# AQS-v4_0.net
KiCad netlist of a schematic drawn in EAGLE
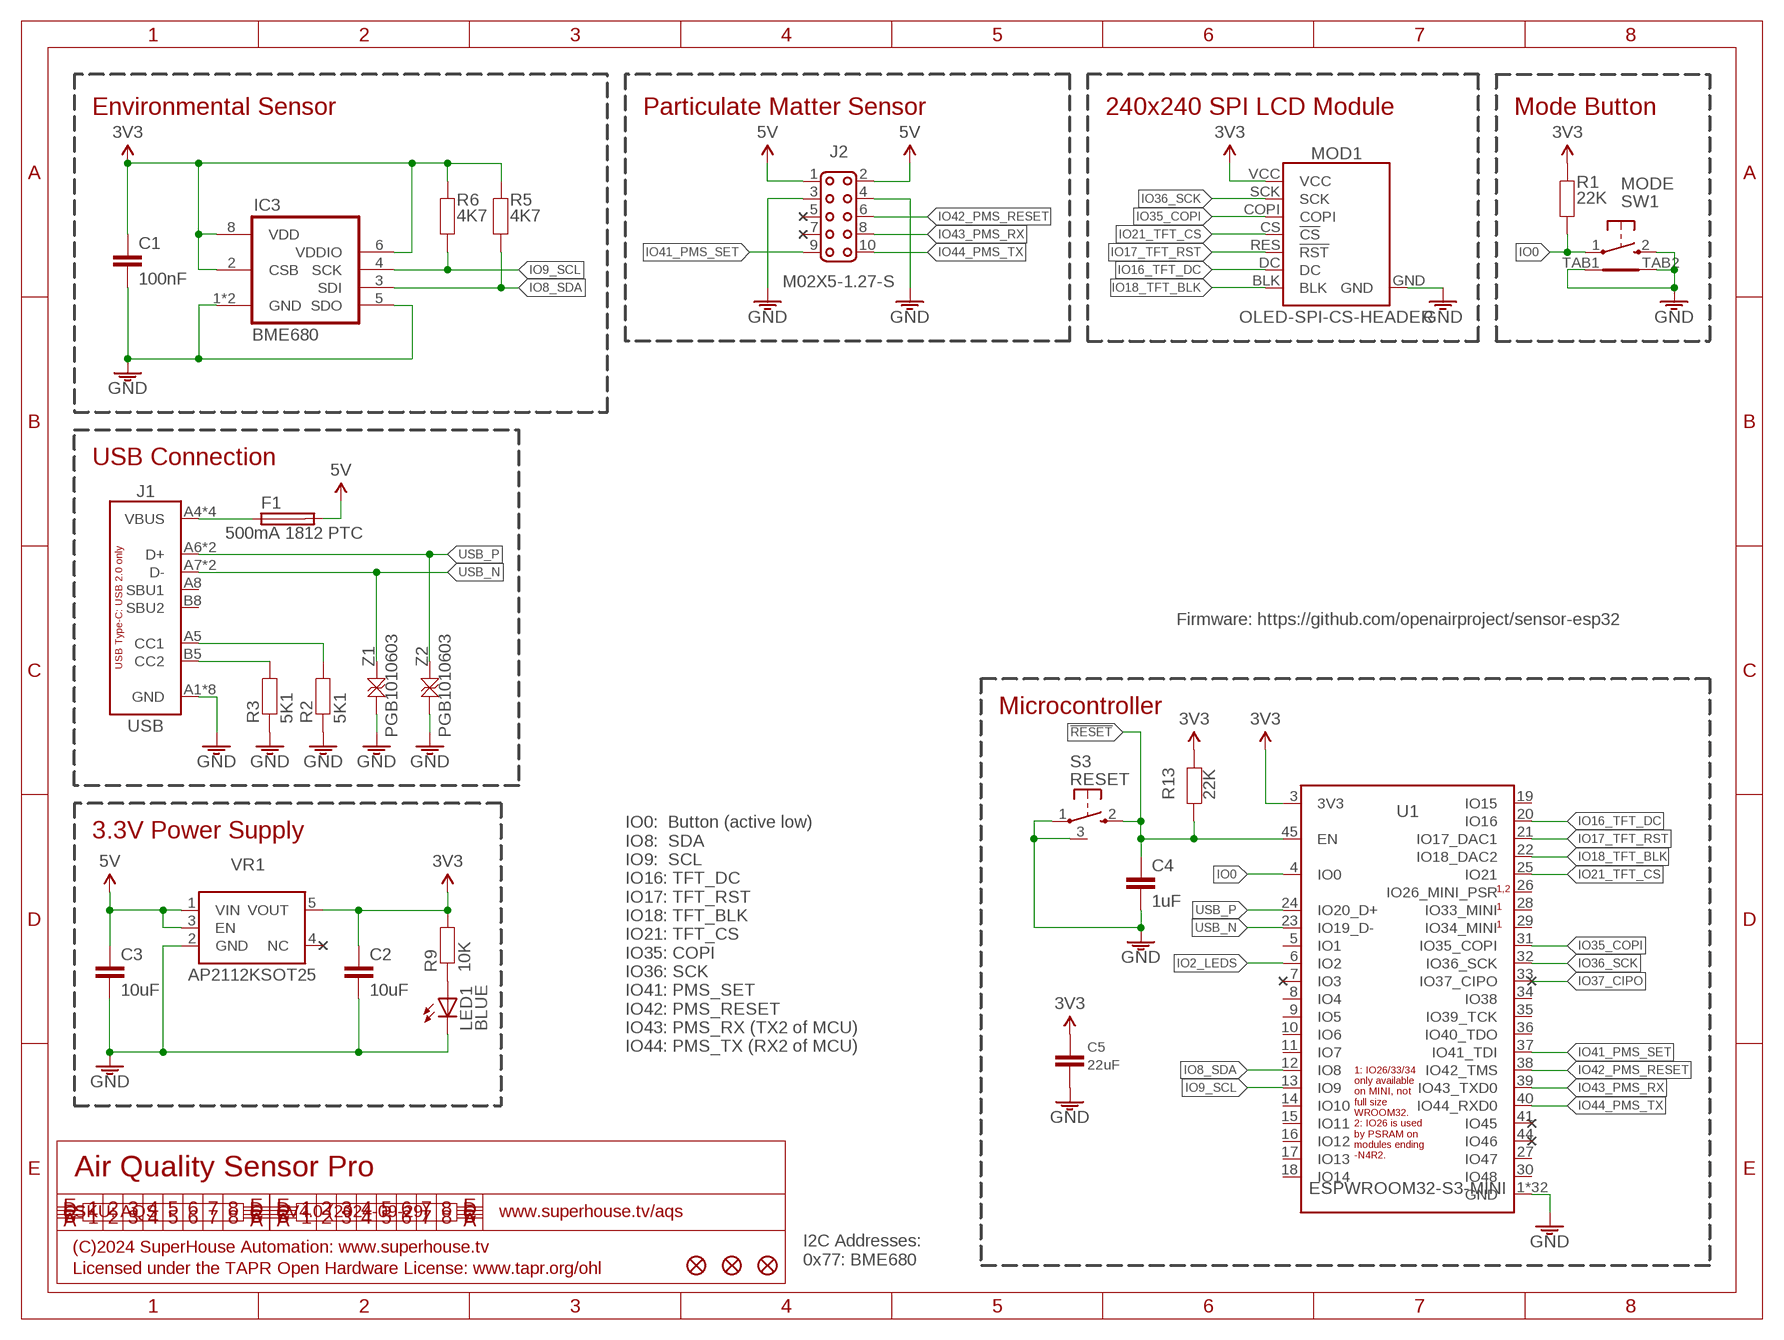
[diagram p0: schematic, sheet 1]

(export (version "E")
  (design (tool "Eeschema 10.0.6"))
  (components
    (comp (ref "C1")
      (value "100nF")
      (footprint "eagle-import:C0603")
      (libsource (lib "eagle-import") (part "CAP0603"))
    )
    (comp (ref "C2")
      (value "10uF")
      (footprint "eagle-import:C0805")
      (libsource (lib "eagle-import") (part "CAP0805"))
    )
    (comp (ref "C3")
      (value "10uF")
      (footprint "eagle-import:C0805")
      (libsource (lib "eagle-import") (part "CAP0805"))
    )
    (comp (ref "C4")
      (value "1uF")
      (footprint "eagle-import:C0603")
      (libsource (lib "eagle-import") (part "CAP0603"))
    )
    (comp (ref "C5")
      (value "22uF")
      (footprint "eagle-import:C0805")
      (libsource (lib "eagle-import") (part "CAP0805"))
    )
    (comp (ref "F1")
      (value "500mA 1812 PTC")
      (footprint "eagle-import:1206")
      (libsource (lib "eagle-import") (part "PTC-1206"))
    )
    (comp (ref "IC3")
      (value "BME680")
      (footprint "eagle-import:BME680")
      (libsource (lib "eagle-import") (part "BME680"))
    )
    (comp (ref "J1")
      (value "USB")
      (footprint "eagle-import:USB-C-VERT")
      (libsource (lib "eagle-import") (part "USB-C-16P-16P-VERT"))
    )
    (comp (ref "J2")
      (value "M02X5-1.27-S")
      (footprint "eagle-import:2X05-1.27-S")
      (libsource (lib "eagle-import") (part "M02X5-1.27-S"))
    )
    (comp (ref "LED1")
      (value "BLUE")
      (footprint "eagle-import:LED-0603")
      (libsource (lib "eagle-import") (part "LED0603"))
    )
    (comp (ref "MOD1")
      (value "OLED-SPI-CS-HEADER")
      (footprint "eagle-import:OLED-240X240-1.54-HEADER")
      (libsource (lib "eagle-import") (part "OLED-SPI-CS-HEADER"))
    )
    (comp (ref "R1")
      (value "22K")
      (footprint "eagle-import:R0603")
      (libsource (lib "eagle-import") (part "RESISTOR0603"))
    )
    (comp (ref "R2")
      (value "5K1")
      (footprint "eagle-import:R0603")
      (libsource (lib "eagle-import") (part "RESISTOR0603"))
    )
    (comp (ref "R3")
      (value "5K1")
      (footprint "eagle-import:R0603")
      (libsource (lib "eagle-import") (part "RESISTOR0603"))
    )
    (comp (ref "R5")
      (value "4K7")
      (footprint "eagle-import:R0603")
      (libsource (lib "eagle-import") (part "RESISTOR0603"))
    )
    (comp (ref "R6")
      (value "4K7")
      (footprint "eagle-import:R0603")
      (libsource (lib "eagle-import") (part "RESISTOR0603"))
    )
    (comp (ref "R9")
      (value "10K")
      (footprint "eagle-import:R0603")
      (libsource (lib "eagle-import") (part "RESISTOR0603"))
    )
    (comp (ref "R13")
      (value "22K")
      (footprint "eagle-import:R0603")
      (libsource (lib "eagle-import") (part "RESISTOR0603"))
    )
    (comp (ref "S3")
      (value "RESET")
      (footprint "eagle-import:TACT-VERT-1TAB")
      (libsource (lib "eagle-import") (part "TAC-SWITCH-1TABGT-TCB73B"))
    )
    (comp (ref "SW1")
      (value "MODE")
      (footprint "eagle-import:TYCO-FSMRAJ")
      (libsource (lib "eagle-import") (part "TAC-SWITCH-2PIN-GND-FSMRAJ"))
    )
    (comp (ref "U$23")
      (value "FIDUCIAL1X2")
      (footprint "eagle-import:FIDUCIAL-1X2")
      (libsource (lib "eagle-import") (part "FIDUCIAL1X2"))
    )
    (comp (ref "U$24")
      (value "FIDUCIAL1X2")
      (footprint "eagle-import:FIDUCIAL-1X2")
      (libsource (lib "eagle-import") (part "FIDUCIAL1X2"))
    )
    (comp (ref "U$25")
      (value "FIDUCIAL1X2")
      (footprint "eagle-import:FIDUCIAL-1X2")
      (libsource (lib "eagle-import") (part "FIDUCIAL1X2"))
    )
    (comp (ref "U1")
      (value "ESPWROOM32-S3-MINI")
      (footprint "eagle-import:ESP32-S3-MINI")
      (libsource (lib "eagle-import") (part "ESPWROOM32-S3-MINI"))
    )
    (comp (ref "VR1")
      (value "AP2112KSOT25")
      (footprint "eagle-import:SOT23-5")
      (libsource (lib "eagle-import") (part "AP2112KSOT25"))
    )
    (comp (ref "Z1")
      (value "PGB1010603")
      (footprint "eagle-import:TVS0603")
      (libsource (lib "eagle-import") (part "TVS0603"))
    )
    (comp (ref "Z2")
      (value "PGB1010603")
      (footprint "eagle-import:TVS0603")
      (libsource (lib "eagle-import") (part "TVS0603"))
    )
  )
  (nets
    (net (code "1") (name "/IO46") (class "Default")
      (node (ref "U1") (pin "44") (pinfunction "IO46_44") (pintype "power_in"))
    )
    (net (code "2") (name "/~{RESET}") (class "Default")
      (node (ref "C4") (pin "1") (pinfunction "1_1") (pintype "passive"))
      (node (ref "R13") (pin "2") (pinfunction "2_2") (pintype "passive"))
      (node (ref "S3") (pin "2") (pinfunction "2_2") (pintype "passive"))
      (node (ref "U1") (pin "45") (pinfunction "EN_45") (pintype "bidirectional"))
    )
    (net (code "3") (name "3.3V") (class "Default")
      (node (ref "C1") (pin "1") (pinfunction "1_1") (pintype "passive"))
      (node (ref "C2") (pin "1") (pinfunction "1_1") (pintype "passive"))
      (node (ref "C5") (pin "1") (pinfunction "1_1") (pintype "passive"))
      (node (ref "IC3") (pin "2") (pinfunction "CSB_2") (pintype "input"))
      (node (ref "IC3") (pin "6") (pinfunction "VDDIO_6") (pintype "power_in"))
      (node (ref "IC3") (pin "8") (pinfunction "VDD_8") (pintype "power_in"))
      (node (ref "MOD1") (pin "VCC") (pinfunction "VCC_VCC") (pintype "bidirectional"))
      (node (ref "R1") (pin "2") (pinfunction "2_2") (pintype "passive"))
      (node (ref "R13") (pin "1") (pinfunction "1_1") (pintype "passive"))
      (node (ref "R5") (pin "2") (pinfunction "2_2") (pintype "passive"))
      (node (ref "R6") (pin "2") (pinfunction "2_2") (pintype "passive"))
      (node (ref "R9") (pin "2") (pinfunction "2_2") (pintype "passive"))
      (node (ref "U1") (pin "3") (pinfunction "3V3_3") (pintype "power_in"))
      (node (ref "VR1") (pin "5") (pinfunction "VOUT_5") (pintype "bidirectional"))
    )
    (net (code "4") (name "5V") (class "Default")
      (node (ref "C3") (pin "1") (pinfunction "1_1") (pintype "passive"))
      (node (ref "F1") (pin "2") (pinfunction "2_2") (pintype "passive"))
      (node (ref "J2") (pin "1") (pinfunction "1_1") (pintype "passive"))
      (node (ref "J2") (pin "2") (pinfunction "2_2") (pintype "passive"))
      (node (ref "VR1") (pin "1") (pinfunction "VIN_1") (pintype "bidirectional"))
      (node (ref "VR1") (pin "3") (pinfunction "EN_3") (pintype "bidirectional"))
    )
    (net (code "5") (name "GND") (class "Default")
      (node (ref "C1") (pin "2") (pinfunction "2_2") (pintype "passive"))
      (node (ref "C2") (pin "2") (pinfunction "2_2") (pintype "passive"))
      (node (ref "C3") (pin "2") (pinfunction "2_2") (pintype "passive"))
      (node (ref "C4") (pin "2") (pinfunction "2_2") (pintype "passive"))
      (node (ref "C5") (pin "2") (pinfunction "2_2") (pintype "passive"))
      (node (ref "IC3") (pin "1") (pinfunction "GND_1") (pintype "power_in"))
      (node (ref "IC3") (pin "5") (pinfunction "SDO_5") (pintype "input"))
      (node (ref "IC3") (pin "7") (pinfunction "GND_7") (pintype "power_in"))
      (node (ref "J1") (pin "A1") (pinfunction "GND_A1") (pintype "power_in"))
      (node (ref "J1") (pin "A12") (pinfunction "GND_A12") (pintype "power_in"))
      (node (ref "J1") (pin "B1") (pinfunction "GND_B1") (pintype "power_in"))
      (node (ref "J1") (pin "B12") (pinfunction "GND_B12") (pintype "power_in"))
      (node (ref "J1") (pin "FIX1") (pinfunction "GND_FIX1") (pintype "power_in"))
      (node (ref "J1") (pin "FIX2") (pinfunction "GND_FIX2") (pintype "power_in"))
      (node (ref "J1") (pin "FIX3") (pinfunction "GND_FIX3") (pintype "power_in"))
      (node (ref "J1") (pin "FIX4") (pinfunction "GND_FIX4") (pintype "power_in"))
      (node (ref "J2") (pin "3") (pinfunction "3_3") (pintype "passive"))
      (node (ref "J2") (pin "4") (pinfunction "4_4") (pintype "passive"))
      (node (ref "LED1") (pin "C") (pinfunction "C_C") (pintype "passive"))
      (node (ref "MOD1") (pin "GND") (pinfunction "GND_GND") (pintype "bidirectional"))
      (node (ref "R2") (pin "1") (pinfunction "1_1") (pintype "passive"))
      (node (ref "R3") (pin "1") (pinfunction "1_1") (pintype "passive"))
      (node (ref "S3") (pin "1") (pinfunction "1_1") (pintype "passive"))
      (node (ref "S3") (pin "3") (pinfunction "3_3") (pintype "passive"))
      (node (ref "SW1") (pin "2") (pinfunction "2_2") (pintype "passive"))
      (node (ref "SW1") (pin "TAB1") (pinfunction "TAB1_TAB1") (pintype "passive"))
      (node (ref "SW1") (pin "TAB2") (pinfunction "TAB2_TAB2") (pintype "passive"))
      (node (ref "U1") (pin "1") (pinfunction "GND_1") (pintype "power_in"))
      (node (ref "U1") (pin "2") (pinfunction "GND_2") (pintype "power_in"))
      (node (ref "U1") (pin "42") (pinfunction "GND_42") (pintype "power_in"))
      (node (ref "U1") (pin "43") (pinfunction "GND_43") (pintype "power_in"))
      (node (ref "U1") (pin "46") (pinfunction "GND_46") (pintype "power_in"))
      (node (ref "U1") (pin "47") (pinfunction "GND_47") (pintype "power_in"))
      (node (ref "U1") (pin "48") (pinfunction "GND_48") (pintype "power_in"))
      (node (ref "U1") (pin "49") (pinfunction "GND_49") (pintype "power_in"))
      (node (ref "U1") (pin "50") (pinfunction "GND_50") (pintype "power_in"))
      (node (ref "U1") (pin "51") (pinfunction "GND_51") (pintype "power_in"))
      (node (ref "U1") (pin "52") (pinfunction "GND_52") (pintype "power_in"))
      (node (ref "U1") (pin "53") (pinfunction "GND_53") (pintype "power_in"))
      (node (ref "U1") (pin "54") (pinfunction "GND_54") (pintype "power_in"))
      (node (ref "U1") (pin "55") (pinfunction "GND_55") (pintype "power_in"))
      (node (ref "U1") (pin "56") (pinfunction "GND_56") (pintype "power_in"))
      (node (ref "U1") (pin "57") (pinfunction "GND_57") (pintype "power_in"))
      (node (ref "U1") (pin "58") (pinfunction "GND_58") (pintype "power_in"))
      (node (ref "U1") (pin "59") (pinfunction "GND_59") (pintype "power_in"))
      (node (ref "U1") (pin "60") (pinfunction "GND_60") (pintype "power_in"))
      (node (ref "U1") (pin "61") (pinfunction "GND_61") (pintype "power_in"))
      (node (ref "U1") (pin "62") (pinfunction "GND_62") (pintype "power_in"))
      (node (ref "U1") (pin "63") (pinfunction "GND_63") (pintype "power_in"))
      (node (ref "U1") (pin "64") (pinfunction "GND_64") (pintype "power_in"))
      (node (ref "U1") (pin "65") (pinfunction "GND_65") (pintype "power_in"))
      (node (ref "U1") (pin "G1") (pinfunction "GND_G1") (pintype "power_in"))
      (node (ref "U1") (pin "G2") (pinfunction "GND_G2") (pintype "power_in"))
      (node (ref "U1") (pin "G3") (pinfunction "GND_G3") (pintype "power_in"))
      (node (ref "U1") (pin "G4") (pinfunction "GND_G4") (pintype "power_in"))
      (node (ref "U1") (pin "G6") (pinfunction "GND_G6") (pintype "power_in"))
      (node (ref "U1") (pin "G7") (pinfunction "GND_G7") (pintype "power_in"))
      (node (ref "U1") (pin "G8") (pinfunction "GND_G8") (pintype "power_in"))
      (node (ref "U1") (pin "G9") (pinfunction "GND_G9") (pintype "power_in"))
      (node (ref "VR1") (pin "2") (pinfunction "GND_2") (pintype "bidirectional"))
      (node (ref "Z1") (pin "1") (pinfunction "1_1") (pintype "passive"))
      (node (ref "Z2") (pin "1") (pinfunction "1_1") (pintype "passive"))
    )
    (net (code "6") (name "IO0") (class "Default")
      (node (ref "R1") (pin "1") (pinfunction "1_1") (pintype "passive"))
      (node (ref "SW1") (pin "1") (pinfunction "1_1") (pintype "passive"))
      (node (ref "U1") (pin "4") (pinfunction "IO0_4") (pintype "bidirectional"))
    )
    (net (code "7") (name "IO2_LEDS") (class "Default")
      (node (ref "U1") (pin "6") (pinfunction "IO2_6") (pintype "bidirectional"))
    )
    (net (code "8") (name "IO8_SDA") (class "Default")
      (node (ref "IC3") (pin "3") (pinfunction "SDI_3") (pintype "bidirectional"))
      (node (ref "R5") (pin "1") (pinfunction "1_1") (pintype "passive"))
      (node (ref "U1") (pin "12") (pinfunction "IO8_12") (pintype "bidirectional"))
    )
    (net (code "9") (name "IO9_SCL") (class "Default")
      (node (ref "IC3") (pin "4") (pinfunction "SCK_4") (pintype "bidirectional"))
      (node (ref "R6") (pin "1") (pinfunction "1_1") (pintype "passive"))
      (node (ref "U1") (pin "13") (pinfunction "IO9_13") (pintype "bidirectional"))
    )
    (net (code "10") (name "IO16_TFT_DC") (class "Default")
      (node (ref "MOD1") (pin "DC") (pinfunction "DC_DC") (pintype "bidirectional"))
      (node (ref "U1") (pin "20") (pinfunction "IO16_20") (pintype "bidirectional"))
    )
    (net (code "11") (name "IO17_TFT_RST") (class "Default")
      (node (ref "MOD1") (pin "RES") (pinfunction "~{RST}_RES") (pintype "bidirectional"))
      (node (ref "U1") (pin "21") (pinfunction "IO17_DAC1_21") (pintype "bidirectional"))
    )
    (net (code "12") (name "IO18_TFT_BLK") (class "Default")
      (node (ref "MOD1") (pin "BLK") (pinfunction "BLK_BLK") (pintype "bidirectional"))
      (node (ref "U1") (pin "22") (pinfunction "IO18_DAC2_22") (pintype "bidirectional"))
    )
    (net (code "13") (name "IO21_TFT_CS") (class "Default")
      (node (ref "MOD1") (pin "CS") (pinfunction "~{CS}_CS") (pintype "bidirectional"))
      (node (ref "U1") (pin "25") (pinfunction "IO21_25") (pintype "bidirectional"))
    )
    (net (code "14") (name "IO35_COPI") (class "Default")
      (node (ref "MOD1") (pin "COPI") (pinfunction "COPI_COPI") (pintype "bidirectional"))
      (node (ref "U1") (pin "31") (pinfunction "IO35_COPI_31") (pintype "bidirectional"))
    )
    (net (code "15") (name "IO36_SCK") (class "Default")
      (node (ref "MOD1") (pin "SCK") (pinfunction "SCK_SCK") (pintype "bidirectional"))
      (node (ref "U1") (pin "32") (pinfunction "IO36_SCK_32") (pintype "bidirectional"))
    )
    (net (code "16") (name "IO37_CIPO") (class "Default")
      (node (ref "U1") (pin "33") (pinfunction "IO37_CIPO_33") (pintype "bidirectional"))
    )
    (net (code "17") (name "IO41_PMS_SET") (class "Default")
      (node (ref "J2") (pin "9") (pinfunction "9_9") (pintype "passive"))
      (node (ref "U1") (pin "37") (pinfunction "IO41_TDI_37") (pintype "bidirectional"))
    )
    (net (code "18") (name "IO42_PMS_RESET") (class "Default")
      (node (ref "J2") (pin "6") (pinfunction "6_6") (pintype "passive"))
      (node (ref "U1") (pin "38") (pinfunction "IO42_TMS_38") (pintype "bidirectional"))
    )
    (net (code "19") (name "IO43_PMS_RX") (class "Default")
      (node (ref "J2") (pin "8") (pinfunction "8_8") (pintype "passive"))
      (node (ref "U1") (pin "39") (pinfunction "IO43_TXD0_39") (pintype "bidirectional"))
    )
    (net (code "20") (name "IO44_PMS_TX") (class "Default")
      (node (ref "J2") (pin "10") (pinfunction "10_10") (pintype "passive"))
      (node (ref "U1") (pin "40") (pinfunction "IO44_RXD0_40") (pintype "bidirectional"))
    )
    (net (code "21") (name "Net-(F1-Pad1)") (class "Default")
      (node (ref "F1") (pin "1") (pinfunction "1_1") (pintype "passive"))
      (node (ref "J1") (pin "A4") (pinfunction "VBUS_A4") (pintype "power_in"))
      (node (ref "J1") (pin "A9") (pinfunction "VBUS_A9") (pintype "power_in"))
      (node (ref "J1") (pin "B4") (pinfunction "VBUS_B4") (pintype "power_in"))
      (node (ref "J1") (pin "B9") (pinfunction "VBUS_B9") (pintype "power_in"))
    )
    (net (code "22") (name "Net-(J1-CC1)") (class "Default")
      (node (ref "J1") (pin "A5") (pinfunction "CC1_A5") (pintype "bidirectional"))
      (node (ref "R2") (pin "2") (pinfunction "2_2") (pintype "passive"))
    )
    (net (code "23") (name "Net-(J1-CC2)") (class "Default")
      (node (ref "J1") (pin "B5") (pinfunction "CC2_B5") (pintype "bidirectional"))
      (node (ref "R3") (pin "2") (pinfunction "2_2") (pintype "passive"))
    )
    (net (code "24") (name "Net-(LED1-PadA)") (class "Default")
      (node (ref "LED1") (pin "A") (pinfunction "A_A") (pintype "passive"))
      (node (ref "R9") (pin "1") (pinfunction "1_1") (pintype "passive"))
    )
    (net (code "25") (name "USB_N") (class "Default")
      (node (ref "J1") (pin "A7") (pinfunction "D-_A7") (pintype "bidirectional"))
      (node (ref "J1") (pin "B7") (pinfunction "D-_B7") (pintype "bidirectional"))
      (node (ref "U1") (pin "23") (pinfunction "IO19_D-_23") (pintype "bidirectional"))
      (node (ref "Z1") (pin "2") (pinfunction "2_2") (pintype "passive"))
    )
    (net (code "26") (name "USB_P") (class "Default")
      (node (ref "J1") (pin "A6") (pinfunction "D+_A6") (pintype "bidirectional"))
      (node (ref "J1") (pin "B6") (pinfunction "D+_B6") (pintype "bidirectional"))
      (node (ref "U1") (pin "24") (pinfunction "IO20_D+_24") (pintype "bidirectional"))
      (node (ref "Z2") (pin "2") (pinfunction "2_2") (pintype "passive"))
    )
    (net (code "27") (name "unconnected-(J1-SBU1-PadA8)") (class "Default")
      (node (ref "J1") (pin "A8") (pinfunction "SBU1_A8") (pintype "bidirectional"))
    )
    (net (code "28") (name "unconnected-(J1-SBU2-PadB8)") (class "Default")
      (node (ref "J1") (pin "B8") (pinfunction "SBU2_B8") (pintype "bidirectional"))
    )
    (net (code "29") (name "unconnected-(J2-Pad5)") (class "Default")
      (node (ref "J2") (pin "5") (pinfunction "5_5") (pintype "passive"))
    )
    (net (code "30") (name "unconnected-(J2-Pad7)") (class "Default")
      (node (ref "J2") (pin "7") (pinfunction "7_7") (pintype "passive"))
    )
    (net (code "31") (name "unconnected-(U1-IO1-Pad5)") (class "Default")
      (node (ref "U1") (pin "5") (pinfunction "IO1_5") (pintype "bidirectional"))
    )
    (net (code "32") (name "unconnected-(U1-IO3-Pad7)") (class "Default")
      (node (ref "U1") (pin "7") (pinfunction "IO3_7") (pintype "bidirectional"))
    )
    (net (code "33") (name "unconnected-(U1-IO4-Pad8)") (class "Default")
      (node (ref "U1") (pin "8") (pinfunction "IO4_8") (pintype "bidirectional"))
    )
    (net (code "34") (name "unconnected-(U1-IO5-Pad9)") (class "Default")
      (node (ref "U1") (pin "9") (pinfunction "IO5_9") (pintype "bidirectional"))
    )
    (net (code "35") (name "unconnected-(U1-IO6-Pad10)") (class "Default")
      (node (ref "U1") (pin "10") (pinfunction "IO6_10") (pintype "bidirectional"))
    )
    (net (code "36") (name "unconnected-(U1-IO7-Pad11)") (class "Default")
      (node (ref "U1") (pin "11") (pinfunction "IO7_11") (pintype "bidirectional"))
    )
    (net (code "37") (name "unconnected-(U1-IO10-Pad14)") (class "Default")
      (node (ref "U1") (pin "14") (pinfunction "IO10_14") (pintype "bidirectional"))
    )
    (net (code "38") (name "unconnected-(U1-IO11-Pad15)") (class "Default")
      (node (ref "U1") (pin "15") (pinfunction "IO11_15") (pintype "bidirectional"))
    )
    (net (code "39") (name "unconnected-(U1-IO12-Pad16)") (class "Default")
      (node (ref "U1") (pin "16") (pinfunction "IO12_16") (pintype "bidirectional"))
    )
    (net (code "40") (name "unconnected-(U1-IO13-Pad17)") (class "Default")
      (node (ref "U1") (pin "17") (pinfunction "IO13_17") (pintype "bidirectional"))
    )
    (net (code "41") (name "unconnected-(U1-IO14-Pad18)") (class "Default")
      (node (ref "U1") (pin "18") (pinfunction "IO14_18") (pintype "bidirectional"))
    )
    (net (code "42") (name "unconnected-(U1-IO15-Pad19)") (class "Default")
      (node (ref "U1") (pin "19") (pinfunction "IO15_19") (pintype "bidirectional"))
    )
    (net (code "43") (name "unconnected-(U1-IO26_MINI_PSR-Pad26)") (class "Default")
      (node (ref "U1") (pin "26") (pinfunction "IO26_MINI_PSR_26") (pintype "bidirectional"))
    )
    (net (code "44") (name "unconnected-(U1-IO33_MINI-Pad28)") (class "Default")
      (node (ref "U1") (pin "28") (pinfunction "IO33_MINI_28") (pintype "bidirectional"))
    )
    (net (code "45") (name "unconnected-(U1-IO34_MINI-Pad29)") (class "Default")
      (node (ref "U1") (pin "29") (pinfunction "IO34_MINI_29") (pintype "bidirectional"))
    )
    (net (code "46") (name "unconnected-(U1-IO38-Pad34)") (class "Default")
      (node (ref "U1") (pin "34") (pinfunction "IO38_34") (pintype "bidirectional"))
    )
    (net (code "47") (name "unconnected-(U1-IO39_TCK-Pad35)") (class "Default")
      (node (ref "U1") (pin "35") (pinfunction "IO39_TCK_35") (pintype "bidirectional"))
    )
    (net (code "48") (name "unconnected-(U1-IO40_TDO-Pad36)") (class "Default")
      (node (ref "U1") (pin "36") (pinfunction "IO40_TDO_36") (pintype "bidirectional"))
    )
    (net (code "49") (name "unconnected-(U1-IO45-Pad41)") (class "Default")
      (node (ref "U1") (pin "41") (pinfunction "IO45_41") (pintype "bidirectional"))
    )
    (net (code "50") (name "unconnected-(U1-IO47-Pad27)") (class "Default")
      (node (ref "U1") (pin "27") (pinfunction "IO47_27") (pintype "bidirectional"))
    )
    (net (code "51") (name "unconnected-(U1-IO48-Pad30)") (class "Default")
      (node (ref "U1") (pin "30") (pinfunction "IO48_30") (pintype "bidirectional"))
    )
    (net (code "52") (name "unconnected-(VR1-NC-Pad4)") (class "Default")
      (node (ref "VR1") (pin "4") (pinfunction "NC_4") (pintype "bidirectional"))
    )
  )
)
